# 2NX_interleaved_boost_converter.net
KiCad netlist of a schematic drawn in EAGLE
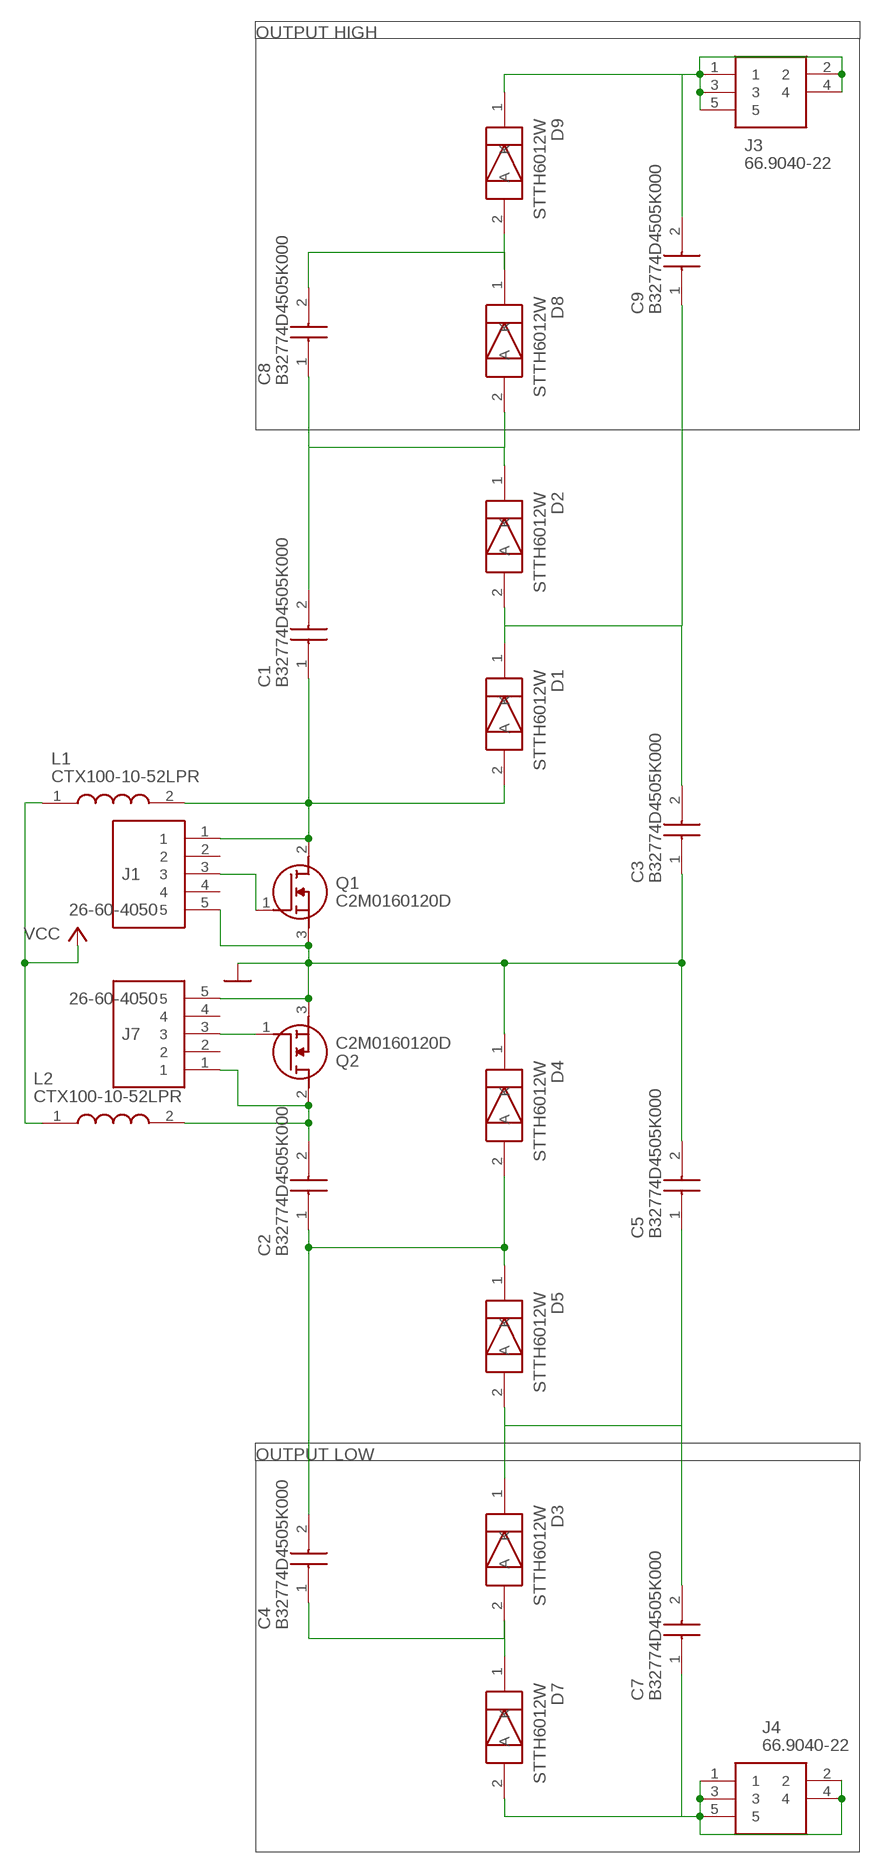
[diagram p0: schematic, sheet 1]
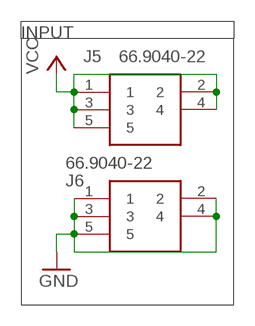
[diagram p1: schematic, sheet 2]

(export (version "E")
  (design (tool "Eeschema 10.0.6"))
  (components
    (comp (ref "C1")
      (value "B32774D4505K000")
      (footprint "eagle-import:B32774D4505K000")
      (fields (field (name "RS_PART_NUMBER") "1726009"))
      (libsource (lib "eagle-import") (part "B32774D4505K000"))
    )
    (comp (ref "C2")
      (value "B32774D4505K000")
      (footprint "eagle-import:B32774D4505K000")
      (fields (field (name "RS_PART_NUMBER") "1726009"))
      (libsource (lib "eagle-import") (part "B32774D4505K000"))
    )
    (comp (ref "C3")
      (value "B32774D4505K000")
      (footprint "eagle-import:B32774D4505K000")
      (fields (field (name "RS_PART_NUMBER") "1726009"))
      (libsource (lib "eagle-import") (part "B32774D4505K000"))
    )
    (comp (ref "C4")
      (value "B32774D4505K000")
      (footprint "eagle-import:B32774D4505K000")
      (fields (field (name "RS_PART_NUMBER") "1726009"))
      (libsource (lib "eagle-import") (part "B32774D4505K000"))
    )
    (comp (ref "C5")
      (value "B32774D4505K000")
      (footprint "eagle-import:B32774D4505K000")
      (fields (field (name "RS_PART_NUMBER") "1726009"))
      (libsource (lib "eagle-import") (part "B32774D4505K000"))
    )
    (comp (ref "C7")
      (value "B32774D4505K000")
      (footprint "eagle-import:B32774D4505K000")
      (fields (field (name "RS_PART_NUMBER") "1726009"))
      (libsource (lib "eagle-import") (part "B32774D4505K000"))
    )
    (comp (ref "C8")
      (value "B32774D4505K000")
      (footprint "eagle-import:B32774D4505K000")
      (fields (field (name "RS_PART_NUMBER") "1726009"))
      (libsource (lib "eagle-import") (part "B32774D4505K000"))
    )
    (comp (ref "C9")
      (value "B32774D4505K000")
      (footprint "eagle-import:B32774D4505K000")
      (fields (field (name "RS_PART_NUMBER") "1726009"))
      (libsource (lib "eagle-import") (part "B32774D4505K000"))
    )
    (comp (ref "D1")
      (value "STTH6012W")
      (footprint "eagle-import:TO1090P515X1560X2445-2P")
      (fields (field (name "RS_PART_NUMBER") "6870818"))
      (libsource (lib "eagle-import") (part "STTH6012W"))
    )
    (comp (ref "D2")
      (value "STTH6012W")
      (footprint "eagle-import:TO1090P515X1560X2445-2P")
      (fields (field (name "RS_PART_NUMBER") "6870818"))
      (libsource (lib "eagle-import") (part "STTH6012W"))
    )
    (comp (ref "D3")
      (value "STTH6012W")
      (footprint "eagle-import:TO1090P515X1560X2445-2P")
      (fields (field (name "RS_PART_NUMBER") "6870818"))
      (libsource (lib "eagle-import") (part "STTH6012W"))
    )
    (comp (ref "D4")
      (value "STTH6012W")
      (footprint "eagle-import:TO1090P515X1560X2445-2P")
      (fields (field (name "RS_PART_NUMBER") "6870818"))
      (libsource (lib "eagle-import") (part "STTH6012W"))
    )
    (comp (ref "D5")
      (value "STTH6012W")
      (footprint "eagle-import:TO1090P515X1560X2445-2P")
      (fields (field (name "RS_PART_NUMBER") "6870818"))
      (libsource (lib "eagle-import") (part "STTH6012W"))
    )
    (comp (ref "D7")
      (value "STTH6012W")
      (footprint "eagle-import:TO1090P515X1560X2445-2P")
      (fields (field (name "RS_PART_NUMBER") "6870818"))
      (libsource (lib "eagle-import") (part "STTH6012W"))
    )
    (comp (ref "D8")
      (value "STTH6012W")
      (footprint "eagle-import:TO1090P515X1560X2445-2P")
      (fields (field (name "RS_PART_NUMBER") "6870818"))
      (libsource (lib "eagle-import") (part "STTH6012W"))
    )
    (comp (ref "D9")
      (value "STTH6012W")
      (footprint "eagle-import:TO1090P515X1560X2445-2P")
      (fields (field (name "RS_PART_NUMBER") "6870818"))
      (libsource (lib "eagle-import") (part "STTH6012W"))
    )
    (comp (ref "J1")
      (value "26-60-4050")
      (footprint "eagle-import:SHDR5W155P0X396_1X5_1966X1001X")
      (fields (field (name "MOUSER_PART_NUMBER") "538-26-60-4050"))
      (libsource (lib "eagle-import") (part "26-60-4050"))
    )
    (comp (ref "J3")
      (value "66.9040-22")
      (footprint "eagle-import:66904022")
      (libsource (lib "eagle-import") (part "66.9040-22"))
    )
    (comp (ref "J4")
      (value "66.9040-22")
      (footprint "eagle-import:66904022")
      (libsource (lib "eagle-import") (part "66.9040-22"))
    )
    (comp (ref "J7")
      (value "26-60-4050")
      (footprint "eagle-import:SHDR5W155P0X396_1X5_1966X1001X")
      (fields (field (name "MOUSER_PART_NUMBER") "538-26-60-4050"))
      (libsource (lib "eagle-import") (part "26-60-4050"))
    )
    (comp (ref "L1")
      (value "CTX100-10-52LPR")
      (footprint "eagle-import:CTX1001052LPR")
      (libsource (lib "eagle-import") (part "CTX100-10-52LPR"))
    )
    (comp (ref "L2")
      (value "CTX100-10-52LPR")
      (footprint "eagle-import:CTX1001052LPR")
      (libsource (lib "eagle-import") (part "CTX100-10-52LPR"))
    )
    (comp (ref "Q1")
      (value "C2M0160120D")
      (footprint "eagle-import:TO544P521X1594X2550-3P")
      (fields (field (name "RS_PART_NUMBER") "1629709"))
      (libsource (lib "eagle-import") (part "C2M0160120D"))
    )
    (comp (ref "Q2")
      (value "C2M0160120D")
      (footprint "eagle-import:TO544P521X1594X2550-3P")
      (fields (field (name "RS_PART_NUMBER") "1629709") (field (name "SPICEPREFIX") "Q"))
      (libsource (lib "eagle-import") (part "C2M0160120D"))
    )
    (comp (ref "J5")
      (value "66.9040-22")
      (footprint "eagle-import:66904022")
      (libsource (lib "eagle-import") (part "66.9040-22"))
    )
    (comp (ref "J6")
      (value "66.9040-22")
      (footprint "eagle-import:66904022")
      (libsource (lib "eagle-import") (part "66.9040-22"))
    )
  )
  (nets
    (net (code "1") (name "GND") (class "Default")
      (node (ref "C3") (pin "1") (pinfunction "1_1") (pintype "bidirectional"))
      (node (ref "C5") (pin "2") (pinfunction "2_2") (pintype "bidirectional"))
      (node (ref "D4") (pin "1") (pinfunction "K_1") (pintype "bidirectional"))
      (node (ref "J1") (pin "5") (pinfunction "5_5") (pintype "bidirectional"))
      (node (ref "J6") (pin "1") (pinfunction "1_1") (pintype "bidirectional"))
      (node (ref "J6") (pin "2") (pinfunction "2_2") (pintype "bidirectional"))
      (node (ref "J6") (pin "3") (pinfunction "3_3") (pintype "bidirectional"))
      (node (ref "J6") (pin "4") (pinfunction "4_4") (pintype "bidirectional"))
      (node (ref "J6") (pin "5") (pinfunction "5_5") (pintype "bidirectional"))
      (node (ref "J7") (pin "5") (pinfunction "5_5") (pintype "bidirectional"))
      (node (ref "Q1") (pin "3") (pinfunction "S_3") (pintype "bidirectional"))
      (node (ref "Q2") (pin "3") (pinfunction "S_3") (pintype "bidirectional"))
    )
    (net (code "2") (name "Net-(D1-A)") (class "Default")
      (node (ref "C1") (pin "1") (pinfunction "1_1") (pintype "bidirectional"))
      (node (ref "D1") (pin "2") (pinfunction "A_2") (pintype "bidirectional"))
      (node (ref "J1") (pin "1") (pinfunction "1_1") (pintype "bidirectional"))
      (node (ref "L1") (pin "2") (pinfunction "2_2") (pintype "bidirectional"))
      (node (ref "Q1") (pin "2") (pinfunction "D_2") (pintype "bidirectional"))
    )
    (net (code "3") (name "Net-(D1-K)") (class "Default")
      (node (ref "C3") (pin "2") (pinfunction "2_2") (pintype "bidirectional"))
      (node (ref "C9") (pin "1") (pinfunction "1_1") (pintype "bidirectional"))
      (node (ref "D1") (pin "1") (pinfunction "K_1") (pintype "bidirectional"))
      (node (ref "D2") (pin "2") (pinfunction "A_2") (pintype "bidirectional"))
    )
    (net (code "4") (name "Net-(D2-K)") (class "Default")
      (node (ref "C1") (pin "2") (pinfunction "2_2") (pintype "bidirectional"))
      (node (ref "C8") (pin "1") (pinfunction "1_1") (pintype "bidirectional"))
      (node (ref "D2") (pin "1") (pinfunction "K_1") (pintype "bidirectional"))
      (node (ref "D8") (pin "2") (pinfunction "A_2") (pintype "bidirectional"))
    )
    (net (code "5") (name "Net-(D3-A)") (class "Default")
      (node (ref "C4") (pin "1") (pinfunction "1_1") (pintype "bidirectional"))
      (node (ref "D3") (pin "2") (pinfunction "A_2") (pintype "bidirectional"))
      (node (ref "D7") (pin "1") (pinfunction "K_1") (pintype "bidirectional"))
    )
    (net (code "6") (name "Net-(D3-K)") (class "Default")
      (node (ref "C5") (pin "1") (pinfunction "1_1") (pintype "bidirectional"))
      (node (ref "C7") (pin "2") (pinfunction "2_2") (pintype "bidirectional"))
      (node (ref "D3") (pin "1") (pinfunction "K_1") (pintype "bidirectional"))
      (node (ref "D5") (pin "2") (pinfunction "A_2") (pintype "bidirectional"))
    )
    (net (code "7") (name "Net-(D4-A)") (class "Default")
      (node (ref "C2") (pin "1") (pinfunction "1_1") (pintype "bidirectional"))
      (node (ref "C4") (pin "2") (pinfunction "2_2") (pintype "bidirectional"))
      (node (ref "D4") (pin "2") (pinfunction "A_2") (pintype "bidirectional"))
      (node (ref "D5") (pin "1") (pinfunction "K_1") (pintype "bidirectional"))
    )
    (net (code "8") (name "Net-(D7-A)") (class "Default")
      (node (ref "C7") (pin "1") (pinfunction "1_1") (pintype "bidirectional"))
      (node (ref "D7") (pin "2") (pinfunction "A_2") (pintype "bidirectional"))
      (node (ref "J4") (pin "1") (pinfunction "1_1") (pintype "bidirectional"))
      (node (ref "J4") (pin "2") (pinfunction "2_2") (pintype "bidirectional"))
      (node (ref "J4") (pin "3") (pinfunction "3_3") (pintype "bidirectional"))
      (node (ref "J4") (pin "4") (pinfunction "4_4") (pintype "bidirectional"))
      (node (ref "J4") (pin "5") (pinfunction "5_5") (pintype "bidirectional"))
    )
    (net (code "9") (name "Net-(D8-K)") (class "Default")
      (node (ref "C8") (pin "2") (pinfunction "2_2") (pintype "bidirectional"))
      (node (ref "D8") (pin "1") (pinfunction "K_1") (pintype "bidirectional"))
      (node (ref "D9") (pin "2") (pinfunction "A_2") (pintype "bidirectional"))
    )
    (net (code "10") (name "Net-(D9-K)") (class "Default")
      (node (ref "C9") (pin "2") (pinfunction "2_2") (pintype "bidirectional"))
      (node (ref "D9") (pin "1") (pinfunction "K_1") (pintype "bidirectional"))
      (node (ref "J3") (pin "1") (pinfunction "1_1") (pintype "bidirectional"))
      (node (ref "J3") (pin "2") (pinfunction "2_2") (pintype "bidirectional"))
      (node (ref "J3") (pin "3") (pinfunction "3_3") (pintype "bidirectional"))
      (node (ref "J3") (pin "4") (pinfunction "4_4") (pintype "bidirectional"))
      (node (ref "J3") (pin "5") (pinfunction "5_5") (pintype "bidirectional"))
    )
    (net (code "11") (name "Net-(Q1-G)") (class "Default")
      (node (ref "J1") (pin "3") (pinfunction "3_3") (pintype "bidirectional"))
      (node (ref "Q1") (pin "1") (pinfunction "G_1") (pintype "bidirectional"))
    )
    (net (code "12") (name "Net-(Q2-D)") (class "Default")
      (node (ref "C2") (pin "2") (pinfunction "2_2") (pintype "bidirectional"))
      (node (ref "J7") (pin "1") (pinfunction "1_1") (pintype "bidirectional"))
      (node (ref "L2") (pin "2") (pinfunction "2_2") (pintype "bidirectional"))
      (node (ref "Q2") (pin "2") (pinfunction "D_2") (pintype "bidirectional"))
    )
    (net (code "13") (name "Net-(Q2-G)") (class "Default")
      (node (ref "J7") (pin "3") (pinfunction "3_3") (pintype "bidirectional"))
      (node (ref "Q2") (pin "1") (pinfunction "G_1") (pintype "bidirectional"))
    )
    (net (code "14") (name "VCC") (class "Default")
      (node (ref "J5") (pin "1") (pinfunction "1_1") (pintype "bidirectional"))
      (node (ref "J5") (pin "2") (pinfunction "2_2") (pintype "bidirectional"))
      (node (ref "J5") (pin "3") (pinfunction "3_3") (pintype "bidirectional"))
      (node (ref "J5") (pin "4") (pinfunction "4_4") (pintype "bidirectional"))
      (node (ref "J5") (pin "5") (pinfunction "5_5") (pintype "bidirectional"))
      (node (ref "L1") (pin "1") (pinfunction "1_1") (pintype "bidirectional"))
      (node (ref "L2") (pin "1") (pinfunction "1_1") (pintype "bidirectional"))
    )
    (net (code "15") (name "unconnected-(J1-Pad2)") (class "Default")
      (node (ref "J1") (pin "2") (pinfunction "2_2") (pintype "bidirectional"))
    )
    (net (code "16") (name "unconnected-(J1-Pad4)") (class "Default")
      (node (ref "J1") (pin "4") (pinfunction "4_4") (pintype "bidirectional"))
    )
    (net (code "17") (name "unconnected-(J7-Pad2)") (class "Default")
      (node (ref "J7") (pin "2") (pinfunction "2_2") (pintype "bidirectional"))
    )
    (net (code "18") (name "unconnected-(J7-Pad4)") (class "Default")
      (node (ref "J7") (pin "4") (pinfunction "4_4") (pintype "bidirectional"))
    )
  )
)
